# Power.net
KiCad netlist of a schematic drawn in Altium Designer
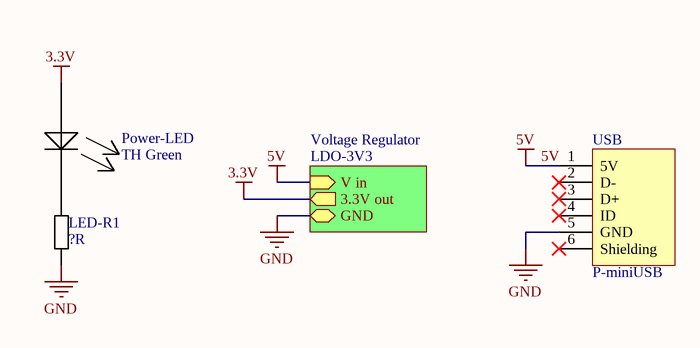
[diagram p0: Power.SchDoc]

(export (version "E")
  (design (tool "Eeschema 10.0.6"))
  (components
    (comp (ref "LED-R1")
      (value "?R")
      (footprint "R 0805 / 2012")
      (libsource (lib "Standard") (part "Resistor"))
    )
    (comp (ref "Power-LED") (value "TH Green") (footprint "LED 3mm") (libsource (lib "LEDs") (part "LED")))
    (comp (ref "USB")
      (value "P-miniUSB")
      (footprint "miniUSB")
      (libsource (lib "Connectors") (part "miniUSB"))
    )
  )
  (nets
    (net (code "1") (name "3.3V") (class "Default")
      (node (ref "Power-LED") (pin "1") (pinfunction "+_1") (pintype "passive"))
    )
    (net (code "2") (name "5V") (class "Default")
      (node (ref "USB") (pin "1") (pinfunction "5V_1") (pintype "passive"))
    )
    (net (code "3") (name "GND") (class "Default")
      (node (ref "LED-R1") (pin "1") (pinfunction "1_1") (pintype "passive"))
      (node (ref "USB") (pin "5") (pinfunction "GND_5") (pintype "passive"))
    )
    (net (code "4") (name "Net-(Power-LED--)") (class "Default")
      (node (ref "LED-R1") (pin "2") (pinfunction "2_2") (pintype "passive"))
      (node (ref "Power-LED") (pin "2") (pinfunction "-_2") (pintype "passive"))
    )
    (net (code "5") (name "unconnected-(USB-D+-Pad3)") (class "Default")
      (node (ref "USB") (pin "3") (pinfunction "D+_3") (pintype "passive+no_connect"))
    )
    (net (code "6") (name "unconnected-(USB-D--Pad2)") (class "Default")
      (node (ref "USB") (pin "2") (pinfunction "D-_2") (pintype "passive+no_connect"))
    )
    (net (code "7") (name "unconnected-(USB-ID-Pad4)") (class "Default")
      (node (ref "USB") (pin "4") (pinfunction "ID_4") (pintype "passive+no_connect"))
    )
    (net (code "8") (name "unconnected-(USB-Shielding-Pad6)") (class "Default")
      (node (ref "USB") (pin "6") (pinfunction "Shielding_6") (pintype "passive+no_connect"))
    )
  )
)
